# IF_SEL.net
KiCad netlist of a schematic drawn in Altium Designer
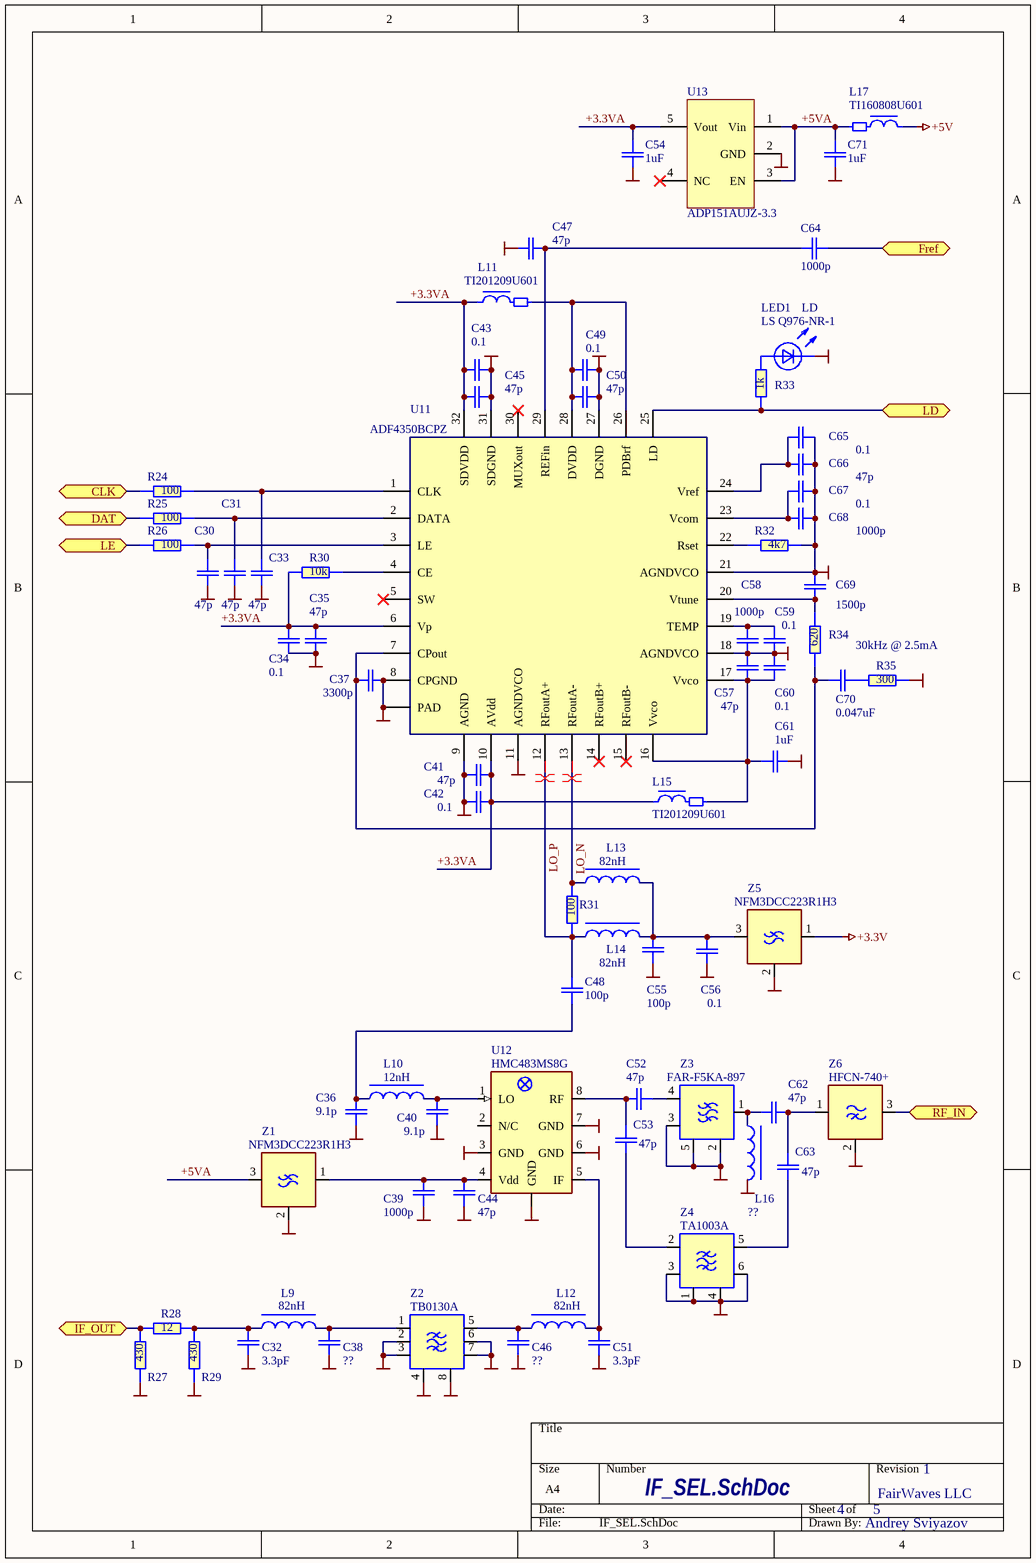
[diagram p0: IF_SEL.SchDoc]

(export (version "E")
  (design (tool "Eeschema 10.0.6"))
  (components
    (comp (ref "C30")
      (value "47p")
      (footprint "C0603-Phillips")
      (description "Capacitor")
      (fields (field (name "MANUFACTURER") "MURATA") (field (name "TOLERANCE") "20%"))
      (libsource (lib "Capacitors") (part "C0603"))
    )
    (comp (ref "C31")
      (value "47p")
      (footprint "C0603-Phillips")
      (description "Capacitor")
      (fields (field (name "MANUFACTURER") "MURATA") (field (name "TOLERANCE") "20%"))
      (libsource (lib "Capacitors") (part "C0603"))
    )
    (comp (ref "C32")
      (value "3.3pF")
      (footprint "C0603-Phillips")
      (description "Capacitor")
      (fields (field (name "MANUFACTURER") "MURATA") (field (name "TOLERANCE") "20%"))
      (libsource (lib "Capacitors") (part "C0603"))
    )
    (comp (ref "C33")
      (value "47p")
      (footprint "C0603-Phillips")
      (description "Capacitor")
      (fields (field (name "MANUFACTURER") "MURATA") (field (name "TOLERANCE") "20%"))
      (libsource (lib "Capacitors") (part "C0603"))
    )
    (comp (ref "C34")
      (value "0.1")
      (footprint "C0603-Phillips")
      (description "Capacitor")
      (fields (field (name "MANUFACTURER") "MURATA") (field (name "TOLERANCE") "20%"))
      (libsource (lib "Capacitors") (part "C0603"))
    )
    (comp (ref "C35")
      (value "47p")
      (footprint "C0603-Phillips")
      (description "Capacitor")
      (fields (field (name "MANUFACTURER") "MURATA") (field (name "TOLERANCE") "20%"))
      (libsource (lib "Capacitors") (part "C0603"))
    )
    (comp (ref "C36")
      (value "9.1p")
      (footprint "C0603-Phillips")
      (description "Capacitor")
      (fields (field (name "MANUFACTURER") "MURATA") (field (name "TOLERANCE") "20%"))
      (libsource (lib "Capacitors") (part "C0603"))
    )
    (comp (ref "C37")
      (value "3300p")
      (footprint "C0603-Phillips")
      (description "Capacitor")
      (fields (field (name "MANUFACTURER") "MURATA") (field (name "TOLERANCE") "20%"))
      (libsource (lib "Capacitors") (part "C0603"))
    )
    (comp (ref "C38")
      (value "??")
      (footprint "C0603-Phillips")
      (description "Capacitor")
      (fields (field (name "MANUFACTURER") "MURATA") (field (name "TOLERANCE") "20%"))
      (libsource (lib "Capacitors") (part "C0603"))
    )
    (comp (ref "C39")
      (value "1000p")
      (footprint "C0603-Phillips")
      (description "Capacitor")
      (fields (field (name "MANUFACTURER") "MURATA") (field (name "TOLERANCE") "20%"))
      (libsource (lib "Capacitors") (part "C0603"))
    )
    (comp (ref "C40")
      (value "9.1p")
      (footprint "C0603-Phillips")
      (description "Capacitor")
      (fields (field (name "MANUFACTURER") "MURATA") (field (name "TOLERANCE") "20%"))
      (libsource (lib "Capacitors") (part "C0603"))
    )
    (comp (ref "C41")
      (value "47p")
      (footprint "C0603-Phillips")
      (description "Capacitor")
      (fields (field (name "MANUFACTURER") "MURATA") (field (name "TOLERANCE") "20%"))
      (libsource (lib "Capacitors") (part "C0603"))
    )
    (comp (ref "C42")
      (value "0.1")
      (footprint "C0603-Phillips")
      (description "Capacitor")
      (fields (field (name "MANUFACTURER") "MURATA") (field (name "TOLERANCE") "20%"))
      (libsource (lib "Capacitors") (part "C0603"))
    )
    (comp (ref "C43")
      (value "0.1")
      (footprint "C0603-Phillips")
      (description "Capacitor")
      (fields (field (name "MANUFACTURER") "MURATA") (field (name "TOLERANCE") "20%"))
      (libsource (lib "Capacitors") (part "C0603"))
    )
    (comp (ref "C44")
      (value "47p")
      (footprint "C0603-Phillips")
      (description "Capacitor")
      (fields (field (name "MANUFACTURER") "MURATA") (field (name "TOLERANCE") "20%"))
      (libsource (lib "Capacitors") (part "C0603"))
    )
    (comp (ref "C45")
      (value "47p")
      (footprint "C0603-Phillips")
      (description "Capacitor")
      (fields (field (name "MANUFACTURER") "MURATA") (field (name "TOLERANCE") "20%"))
      (libsource (lib "Capacitors") (part "C0603"))
    )
    (comp (ref "C46")
      (value "??")
      (footprint "C0603-Phillips")
      (description "Capacitor")
      (fields (field (name "MANUFACTURER") "MURATA") (field (name "TOLERANCE") "20%"))
      (libsource (lib "Capacitors") (part "C0603"))
    )
    (comp (ref "C47")
      (value "47p")
      (footprint "C0603-Phillips")
      (description "Capacitor")
      (fields (field (name "MANUFACTURER") "MURATA") (field (name "TOLERANCE") "20%"))
      (libsource (lib "Capacitors") (part "C0603"))
    )
    (comp (ref "C48")
      (value "100p")
      (footprint "C0603-Phillips")
      (description "Capacitor")
      (fields (field (name "MANUFACTURER") "MURATA") (field (name "TOLERANCE") "20%"))
      (libsource (lib "Capacitors") (part "C0603"))
    )
    (comp (ref "C49")
      (value "0.1")
      (footprint "C0603-Phillips")
      (description "Capacitor")
      (fields (field (name "MANUFACTURER") "MURATA") (field (name "TOLERANCE") "20%"))
      (libsource (lib "Capacitors") (part "C0603"))
    )
    (comp (ref "C50")
      (value "47p")
      (footprint "C0603-Phillips")
      (description "Capacitor")
      (fields (field (name "MANUFACTURER") "MURATA") (field (name "TOLERANCE") "20%"))
      (libsource (lib "Capacitors") (part "C0603"))
    )
    (comp (ref "C51")
      (value "3.3pF")
      (footprint "C0603-Phillips")
      (description "Capacitor")
      (fields (field (name "MANUFACTURER") "MURATA") (field (name "TOLERANCE") "20%"))
      (libsource (lib "Capacitors") (part "C0603"))
    )
    (comp (ref "C52")
      (value "47p")
      (footprint "C0603-Phillips")
      (description "Capacitor")
      (fields (field (name "MANUFACTURER") "MURATA") (field (name "TOLERANCE") "20%"))
      (libsource (lib "Capacitors") (part "C0603"))
    )
    (comp (ref "C53")
      (value "47p")
      (footprint "C0603-Phillips")
      (description "Capacitor")
      (fields (field (name "MANUFACTURER") "MURATA") (field (name "TOLERANCE") "20%"))
      (libsource (lib "Capacitors") (part "C0603"))
    )
    (comp (ref "C54")
      (value "1uF")
      (footprint "C0603-Phillips")
      (description "Capacitor")
      (fields (field (name "MANUFACTURER") "MURATA") (field (name "TOLERANCE") "20%"))
      (libsource (lib "Capacitors") (part "C0603"))
    )
    (comp (ref "C55")
      (value "100p")
      (footprint "C0603-Phillips")
      (description "Capacitor")
      (fields (field (name "MANUFACTURER") "MURATA") (field (name "TOLERANCE") "20%"))
      (libsource (lib "Capacitors") (part "C0603"))
    )
    (comp (ref "C56")
      (value "0.1")
      (footprint "C0603-Phillips")
      (description "Capacitor")
      (fields (field (name "MANUFACTURER") "MURATA") (field (name "TOLERANCE") "20%"))
      (libsource (lib "Capacitors") (part "C0603"))
    )
    (comp (ref "C57")
      (value "47p")
      (footprint "C0603-Phillips")
      (description "Capacitor")
      (fields (field (name "MANUFACTURER") "MURATA") (field (name "TOLERANCE") "20%"))
      (libsource (lib "Capacitors") (part "C0603"))
    )
    (comp (ref "C58")
      (value "1000p")
      (footprint "C0603-Phillips")
      (description "Capacitor")
      (fields (field (name "MANUFACTURER") "MURATA") (field (name "TOLERANCE") "20%"))
      (libsource (lib "Capacitors") (part "C0603"))
    )
    (comp (ref "C59")
      (value "0.1")
      (footprint "C0603-Phillips")
      (description "Capacitor")
      (fields (field (name "MANUFACTURER") "MURATA") (field (name "TOLERANCE") "20%"))
      (libsource (lib "Capacitors") (part "C0603"))
    )
    (comp (ref "C60")
      (value "0.1")
      (footprint "C0603-Phillips")
      (description "Capacitor")
      (fields (field (name "MANUFACTURER") "MURATA") (field (name "TOLERANCE") "20%"))
      (libsource (lib "Capacitors") (part "C0603"))
    )
    (comp (ref "C61")
      (value "1uF")
      (footprint "C0603-Phillips")
      (description "Capacitor")
      (fields (field (name "MANUFACTURER") "MURATA") (field (name "TOLERANCE") "20%"))
      (libsource (lib "Capacitors") (part "C0603"))
    )
    (comp (ref "C62")
      (value "47p")
      (footprint "C0603-Phillips")
      (description "Capacitor")
      (fields (field (name "MANUFACTURER") "MURATA") (field (name "TOLERANCE") "20%"))
      (libsource (lib "Capacitors") (part "C0603"))
    )
    (comp (ref "C63")
      (value "47p")
      (footprint "C0603-Phillips")
      (description "Capacitor")
      (fields (field (name "MANUFACTURER") "MURATA") (field (name "TOLERANCE") "20%"))
      (libsource (lib "Capacitors") (part "C0603"))
    )
    (comp (ref "C64")
      (value "1000p")
      (footprint "C0603-Phillips")
      (description "Capacitor")
      (fields (field (name "MANUFACTURER") "MURATA") (field (name "TOLERANCE") "20%"))
      (libsource (lib "Capacitors") (part "C0603"))
    )
    (comp (ref "C65")
      (value "0.1")
      (footprint "C0603-Phillips")
      (description "Capacitor")
      (fields (field (name "MANUFACTURER") "MURATA") (field (name "TOLERANCE") "20%"))
      (libsource (lib "Capacitors") (part "C0603"))
    )
    (comp (ref "C66")
      (value "47p")
      (footprint "C0603-Phillips")
      (description "Capacitor")
      (fields (field (name "MANUFACTURER") "MURATA") (field (name "TOLERANCE") "20%"))
      (libsource (lib "Capacitors") (part "C0603"))
    )
    (comp (ref "C67")
      (value "0.1")
      (footprint "C0603-Phillips")
      (description "Capacitor")
      (fields (field (name "MANUFACTURER") "MURATA") (field (name "TOLERANCE") "20%"))
      (libsource (lib "Capacitors") (part "C0603"))
    )
    (comp (ref "C68")
      (value "1000p")
      (footprint "C0603-Phillips")
      (description "Capacitor")
      (fields (field (name "MANUFACTURER") "MURATA") (field (name "TOLERANCE") "20%"))
      (libsource (lib "Capacitors") (part "C0603"))
    )
    (comp (ref "C69")
      (value "1500p")
      (footprint "C0603-Phillips")
      (description "Capacitor")
      (fields (field (name "MANUFACTURER") "MURATA") (field (name "TOLERANCE") "20%"))
      (libsource (lib "Capacitors") (part "C0603"))
    )
    (comp (ref "C70")
      (value "0.047uF")
      (footprint "C0603-Phillips")
      (description "Capacitor")
      (fields (field (name "MANUFACTURER") "MURATA") (field (name "TOLERANCE") "20%"))
      (libsource (lib "Capacitors") (part "C0603"))
    )
    (comp (ref "C71")
      (value "1uF")
      (footprint "C0603-Phillips")
      (description "Capacitor")
      (fields (field (name "MANUFACTURER") "MURATA") (field (name "TOLERANCE") "20%"))
      (libsource (lib "Capacitors") (part "C0603"))
    )
    (comp (ref "L9")
      (value "82nH")
      (footprint "TF160808-Phillips")
      (description "Coil")
      (fields (field (name "MANUFACTURER") "SMD"))
      (libsource (lib "Inductance Transformers") (part "TF160808"))
    )
    (comp (ref "L10")
      (value "12nH")
      (footprint "TF160808-Phillips")
      (description "Coil")
      (fields (field (name "MANUFACTURER") "SMD"))
      (libsource (lib "") (part "TF160808_1"))
    )
    (comp (ref "L11")
      (value "TI201209U601")
      (footprint "TI2012-Phillips")
      (description "Choke")
      (fields (field (name "MANUFACTURER") "MURATA"))
      (libsource (lib "Andy") (part "TI2012_1"))
    )
    (comp (ref "L12")
      (value "82nH")
      (footprint "TF160808-Phillips")
      (description "Coil")
      (fields (field (name "MANUFACTURER") "SMD"))
      (libsource (lib "Inductance Transformers") (part "TF160808"))
    )
    (comp (ref "L13")
      (value "82nH")
      (footprint "TF160808-Phillips")
      (description "Coil")
      (fields (field (name "MANUFACTURER") "SMD"))
      (libsource (lib "Inductance Transformers") (part "TF160808"))
    )
    (comp (ref "L14")
      (value "82nH")
      (footprint "TF160808-Phillips")
      (description "Coil")
      (fields (field (name "MANUFACTURER") "SMD"))
      (libsource (lib "Inductance Transformers") (part "TF160808"))
    )
    (comp (ref "L15")
      (value "TI201209U601")
      (footprint "TI2012-Phillips")
      (description "Choke")
      (fields (field (name "MANUFACTURER") "MURATA"))
      (libsource (lib "Andy") (part "TI2012_1"))
    )
    (comp (ref "L16")
      (value "??")
      (footprint "TF160808-Phillips")
      (description "Coil")
      (fields (field (name "MANUFACTURER") "SMD"))
      (libsource (lib "Inductance Transformers") (part "TF160808"))
    )
    (comp (ref "L17")
      (value "TI160808U601")
      (footprint "Andy:Ti160808-Phillips")
      (description "Choke")
      (fields (field (name "MANUFACTURER") "MURATA"))
      (libsource (lib "altium-import") (part "root_0_mirrored_TI160808_"))
    )
    (comp (ref "LED1")
      (value "LS Q976-NR-1")
      (footprint "LED-0603y")
      (description "LED SMD")
      (fields (field (name "MANUFACTURER") "OSRAM Opto Semi") (field (name "MISC") "LD"))
      (libsource (lib "altium-import") (part "root_1_mirrored_LED0603_"))
    )
    (comp (ref "R24")
      (value "100")
      (footprint "R0603-PHILLIPS")
      (description "Resistor")
      (fields (field (name "MANUFACTURER") "YAGEO") (field (name "TOLERANCE") "5%"))
      (libsource (lib "altium-import") (part "root_1_R0603_"))
    )
    (comp (ref "R25")
      (value "100")
      (footprint "R0603-PHILLIPS")
      (description "Resistor")
      (fields (field (name "MANUFACTURER") "YAGEO") (field (name "TOLERANCE") "5%"))
      (libsource (lib "altium-import") (part "root_1_R0603_"))
    )
    (comp (ref "R26")
      (value "100")
      (footprint "R0603-PHILLIPS")
      (description "Resistor")
      (fields (field (name "MANUFACTURER") "YAGEO") (field (name "TOLERANCE") "5%"))
      (libsource (lib "altium-import") (part "root_1_R0603_"))
    )
    (comp (ref "R27")
      (value "430")
      (footprint "R0603-PHILLIPS")
      (description "Resistor")
      (fields (field (name "MANUFACTURER") "YAGEO") (field (name "TOLERANCE") "5%"))
      (libsource (lib "altium-import") (part "root_2_R0603_"))
    )
    (comp (ref "R28")
      (value "12")
      (footprint "R0603-PHILLIPS")
      (description "Resistor")
      (fields (field (name "MANUFACTURER") "YAGEO") (field (name "TOLERANCE") "5%"))
      (libsource (lib "altium-import") (part "root_1_R0603_"))
    )
    (comp (ref "R29")
      (value "430")
      (footprint "R0603-PHILLIPS")
      (description "Resistor")
      (fields (field (name "MANUFACTURER") "YAGEO") (field (name "TOLERANCE") "5%"))
      (libsource (lib "altium-import") (part "root_2_R0603_"))
    )
    (comp (ref "R30")
      (value "10k")
      (footprint "R0603-PHILLIPS")
      (description "Resistor")
      (fields (field (name "MANUFACTURER") "YAGEO") (field (name "TOLERANCE") "5%"))
      (libsource (lib "altium-import") (part "root_1_R0603_"))
    )
    (comp (ref "R31")
      (value "100")
      (footprint "R0603-PHILLIPS")
      (description "Resistor")
      (fields (field (name "MANUFACTURER") "YAGEO") (field (name "TOLERANCE") "5%"))
      (libsource (lib "altium-import") (part "root_2_R0603_"))
    )
    (comp (ref "R32")
      (value "4k7")
      (footprint "R0603-PHILLIPS")
      (description "Resistor")
      (fields (field (name "MANUFACTURER") "YAGEO") (field (name "TOLERANCE") "5%"))
      (libsource (lib "altium-import") (part "root_1_R0603_"))
    )
    (comp (ref "R33")
      (value "1k")
      (footprint "R0603-PHILLIPS")
      (description "Resistor")
      (fields (field (name "MANUFACTURER") "YAGEO") (field (name "TOLERANCE") "5%"))
      (libsource (lib "altium-import") (part "root_2_R0603_"))
    )
    (comp (ref "R34")
      (value "620")
      (footprint "R0603-PHILLIPS")
      (description "Resistor")
      (fields (field (name "MANUFACTURER") "YAGEO") (field (name "TOLERANCE") "5%"))
      (libsource (lib "altium-import") (part "root_2_R0603_"))
    )
    (comp (ref "R35")
      (value "300")
      (footprint "R0603-PHILLIPS")
      (description "Resistor")
      (fields (field (name "MANUFACTURER") "YAGEO") (field (name "TOLERANCE") "5%"))
      (libsource (lib "altium-import") (part "root_1_R0603_"))
    )
    (comp (ref "U11")
      (value "ADF4350BCPZ")
      (footprint "CP-32-2")
      (description "IC")
      (fields (field (name "MANUFACTURER") "Analog Devices"))
      (libsource (lib "Andy") (part "ADF4350BCPZ"))
    )
    (comp (ref "U12")
      (value "HMC483MS8G")
      (footprint "MS8G")
      (description "IC")
      (fields (field (name "MANUFACTURER") "Hittite"))
      (libsource (lib "MicroCircuits") (part "HMC483_5MS8G"))
    )
    (comp (ref "U13")
      (value "ADP151AUJZ-3.3")
      (footprint "SOT-23-5[3.1x1.8/0.95]")
      (description "IC")
      (fields (field (name "MANUFACTURER") "AD"))
      (libsource (lib "Andy") (part "ADP151AUJZ"))
    )
    (comp (ref "Z1")
      (value "NFM3DCC223R1H3")
      (footprint "NFM3DC")
      (description "EMI_FILTER")
      (fields (field (name "MANUFACTURER") "Murata"))
      (libsource (lib "Andy") (part "NFM3DC"))
    )
    (comp (ref "Z2")
      (value "TB0130A")
      (footprint "DCC8_5x5")
      (description "SAW filter")
      (fields (field (name "MANUFACTURER") "Tai-SAW"))
      (libsource (lib "Andy") (part "SAW 5x5-8 SMD"))
    )
    (comp (ref "Z3")
      (value "FAR-F5KA-897")
      (footprint "SAW-1.4x1x0.5mm")
      (description "SAW Filter")
      (fields (field (name "MANUFACTURER") "Taiyo Yuden"))
      (libsource (lib "Andy") (part "SAW 1.4x1.0-5 SMD"))
    )
    (comp (ref "Z4")
      (value "TA1003A")
      (footprint "DCC6C_L")
      (description "SAW filter")
      (fields (field (name "MANUFACTURER") "Tai-SAW"))
      (libsource (lib "Andy") (part "SAW 3x3 SMD"))
    )
    (comp (ref "Z5")
      (value "NFM3DCC223R1H3")
      (footprint "NFM3DC")
      (description "EMI_FILTER")
      (fields (field (name "MANUFACTURER") "Murata"))
      (libsource (lib "Andy") (part "NFM3DC"))
    )
    (comp (ref "Z6")
      (value "HFCN-740+")
      (footprint "LFCN-HFCN")
      (description "High pass filter")
      (fields (field (name "MANUFACTURER") "MiniCircuits"))
      (libsource (lib "Andy") (part "HFCN-2700"))
    )
  )
  (nets
    (net (code "1") (name "+3.3V") (class "Default")
      (node (ref "Z5") (pin "1") (pinfunction "1_1") (pintype "passive"))
    )
    (net (code "2") (name "+5V") (class "Default")
      (node (ref "L17") (pin "1") (pinfunction "1_1") (pintype "passive"))
    )
    (net (code "3") (name "/+3.3VA") (class "Default")
      (node (ref "C34") (pin "2") (pinfunction "2_2") (pintype "passive"))
      (node (ref "C35") (pin "2") (pinfunction "2_2") (pintype "passive"))
      (node (ref "C41") (pin "1") (pinfunction "1_1") (pintype "passive"))
      (node (ref "C42") (pin "1") (pinfunction "1_1") (pintype "passive"))
      (node (ref "C43") (pin "1") (pinfunction "1_1") (pintype "passive"))
      (node (ref "C45") (pin "1") (pinfunction "1_1") (pintype "passive"))
      (node (ref "C54") (pin "2") (pinfunction "2_2") (pintype "passive"))
      (node (ref "L11") (pin "1") (pinfunction "1_1") (pintype "passive"))
      (node (ref "L15") (pin "1") (pinfunction "1_1") (pintype "passive"))
      (node (ref "R30") (pin "1") (pinfunction "1_1") (pintype "passive"))
      (node (ref "U11") (pin "10") (pinfunction "AVdd_10") (pintype "power_in"))
      (node (ref "U11") (pin "32") (pinfunction "SDVDD_32") (pintype "power_in"))
      (node (ref "U11") (pin "6") (pinfunction "Vp_6") (pintype "passive"))
      (node (ref "U13") (pin "5") (pinfunction "Vout_5") (pintype "passive"))
    )
    (net (code "4") (name "/+5VA") (class "Default")
      (node (ref "C71") (pin "2") (pinfunction "2_2") (pintype "passive"))
      (node (ref "L17") (pin "2") (pinfunction "2_2") (pintype "passive"))
      (node (ref "U13") (pin "1") (pinfunction "Vin_1") (pintype "passive"))
      (node (ref "U13") (pin "3") (pinfunction "EN_3") (pintype "passive"))
      (node (ref "Z1") (pin "3") (pinfunction "3_3") (pintype "passive"))
    )
    (net (code "5") (name "/CLK") (class "Default")
      (node (ref "R24") (pin "1") (pinfunction "1_1") (pintype "passive"))
    )
    (net (code "6") (name "/DAT") (class "Default")
      (node (ref "R25") (pin "1") (pinfunction "1_1") (pintype "passive"))
    )
    (net (code "7") (name "/Fref") (class "Default")
      (node (ref "C64") (pin "2") (pinfunction "2_2") (pintype "passive"))
    )
    (net (code "8") (name "/IF_OUT") (class "Default")
      (node (ref "R27") (pin "2") (pinfunction "2_2") (pintype "passive"))
      (node (ref "R28") (pin "1") (pinfunction "1_1") (pintype "passive"))
    )
    (net (code "9") (name "/LD") (class "Default")
      (node (ref "R33") (pin "1") (pinfunction "1_1") (pintype "passive"))
      (node (ref "U11") (pin "25") (pinfunction "LD_25") (pintype "passive"))
    )
    (net (code "10") (name "/LE") (class "Default")
      (node (ref "R26") (pin "1") (pinfunction "1_1") (pintype "passive"))
    )
    (net (code "11") (name "/LO_N") (class "Default")
      (node (ref "L13") (pin "1") (pinfunction "1_1") (pintype "passive"))
      (node (ref "R31") (pin "2") (pinfunction "2_2") (pintype "passive"))
      (node (ref "U11") (pin "13") (pinfunction "RFoutA-_13") (pintype "passive"))
    )
    (net (code "12") (name "/LO_P") (class "Default")
      (node (ref "C48") (pin "1") (pinfunction "1_1") (pintype "passive"))
      (node (ref "L14") (pin "1") (pinfunction "1_1") (pintype "passive"))
      (node (ref "R31") (pin "1") (pinfunction "1_1") (pintype "passive"))
      (node (ref "U11") (pin "12") (pinfunction "RFoutA+_12") (pintype "passive"))
    )
    (net (code "13") (name "/RF_IN") (class "Default")
      (node (ref "Z6") (pin "3") (pinfunction "3_3") (pintype "passive"))
    )
    (net (code "14") (name "GND") (class "Default")
      (node (ref "C30") (pin "1") (pinfunction "1_1") (pintype "passive"))
      (node (ref "C31") (pin "1") (pinfunction "1_1") (pintype "passive"))
      (node (ref "C32") (pin "1") (pinfunction "1_1") (pintype "passive"))
      (node (ref "C33") (pin "1") (pinfunction "1_1") (pintype "passive"))
      (node (ref "C34") (pin "1") (pinfunction "1_1") (pintype "passive"))
      (node (ref "C35") (pin "1") (pinfunction "1_1") (pintype "passive"))
      (node (ref "C36") (pin "2") (pinfunction "2_2") (pintype "passive"))
      (node (ref "C37") (pin "1") (pinfunction "1_1") (pintype "passive"))
      (node (ref "C38") (pin "1") (pinfunction "1_1") (pintype "passive"))
      (node (ref "C39") (pin "2") (pinfunction "2_2") (pintype "passive"))
      (node (ref "C40") (pin "2") (pinfunction "2_2") (pintype "passive"))
      (node (ref "C41") (pin "2") (pinfunction "2_2") (pintype "passive"))
      (node (ref "C42") (pin "2") (pinfunction "2_2") (pintype "passive"))
      (node (ref "C43") (pin "2") (pinfunction "2_2") (pintype "passive"))
      (node (ref "C44") (pin "2") (pinfunction "2_2") (pintype "passive"))
      (node (ref "C45") (pin "2") (pinfunction "2_2") (pintype "passive"))
      (node (ref "C46") (pin "1") (pinfunction "1_1") (pintype "passive"))
      (node (ref "C47") (pin "1") (pinfunction "1_1") (pintype "passive"))
      (node (ref "C49") (pin "2") (pinfunction "2_2") (pintype "passive"))
      (node (ref "C50") (pin "2") (pinfunction "2_2") (pintype "passive"))
      (node (ref "C51") (pin "1") (pinfunction "1_1") (pintype "passive"))
      (node (ref "C54") (pin "1") (pinfunction "1_1") (pintype "passive"))
      (node (ref "C55") (pin "2") (pinfunction "2_2") (pintype "passive"))
      (node (ref "C56") (pin "1") (pinfunction "1_1") (pintype "passive"))
      (node (ref "C57") (pin "2") (pinfunction "2_2") (pintype "passive"))
      (node (ref "C58") (pin "1") (pinfunction "1_1") (pintype "passive"))
      (node (ref "C59") (pin "1") (pinfunction "1_1") (pintype "passive"))
      (node (ref "C60") (pin "2") (pinfunction "2_2") (pintype "passive"))
      (node (ref "C61") (pin "1") (pinfunction "1_1") (pintype "passive"))
      (node (ref "C65") (pin "2") (pinfunction "2_2") (pintype "passive"))
      (node (ref "C66") (pin "2") (pinfunction "2_2") (pintype "passive"))
      (node (ref "C67") (pin "2") (pinfunction "2_2") (pintype "passive"))
      (node (ref "C68") (pin "2") (pinfunction "2_2") (pintype "passive"))
      (node (ref "C69") (pin "2") (pinfunction "2_2") (pintype "passive"))
      (node (ref "C71") (pin "1") (pinfunction "1_1") (pintype "passive"))
      (node (ref "L16") (pin "2") (pinfunction "2_2") (pintype "passive"))
      (node (ref "LED1") (pin "1") (pinfunction "K_1") (pintype "passive"))
      (node (ref "R27") (pin "1") (pinfunction "1_1") (pintype "passive"))
      (node (ref "R29") (pin "1") (pinfunction "1_1") (pintype "passive"))
      (node (ref "R32") (pin "2") (pinfunction "2_2") (pintype "passive"))
      (node (ref "R35") (pin "2") (pinfunction "2_2") (pintype "passive"))
      (node (ref "U11") (pin "0") (pinfunction "PAD_0") (pintype "passive"))
      (node (ref "U11") (pin "11") (pinfunction "AGNDVCO_11") (pintype "power_in"))
      (node (ref "U11") (pin "18") (pinfunction "AGNDVCO_18") (pintype "power_in"))
      (node (ref "U11") (pin "21") (pinfunction "AGNDVCO_21") (pintype "power_in"))
      (node (ref "U11") (pin "27") (pinfunction "DGND_27") (pintype "power_in"))
      (node (ref "U11") (pin "31") (pinfunction "SDGND_31") (pintype "power_in"))
      (node (ref "U11") (pin "8") (pinfunction "CPGND_8") (pintype "passive"))
      (node (ref "U11") (pin "9") (pinfunction "AGND_9") (pintype "power_in"))
      (node (ref "U12") (pin "0") (pinfunction "GND_0") (pintype "power_in"))
      (node (ref "U12") (pin "3") (pinfunction "GND_3") (pintype "power_in"))
      (node (ref "U12") (pin "6") (pinfunction "GND_6") (pintype "power_in"))
      (node (ref "U12") (pin "7") (pinfunction "GND_7") (pintype "power_in"))
      (node (ref "U13") (pin "2") (pinfunction "GND_2") (pintype "passive"))
      (node (ref "Z1") (pin "2") (pinfunction "2_2") (pintype "passive"))
      (node (ref "Z2") (pin "2") (pinfunction "In2_2") (pintype "power_in"))
      (node (ref "Z2") (pin "3") (pinfunction "In3_3") (pintype "power_in"))
      (node (ref "Z2") (pin "4") (pinfunction "Gnd_4") (pintype "power_in"))
      (node (ref "Z2") (pin "6") (pinfunction "Out2_6") (pintype "power_in"))
      (node (ref "Z2") (pin "7") (pinfunction "Out3_7") (pintype "power_in"))
      (node (ref "Z2") (pin "8") (pinfunction "Gnd_8") (pintype "power_in"))
      (node (ref "Z3") (pin "2") (pinfunction "GND_2") (pintype "power_in"))
      (node (ref "Z3") (pin "3") (pinfunction "~{Out}_3") (pintype "passive"))
      (node (ref "Z3") (pin "5") (pinfunction "GND_5") (pintype "power_in"))
      (node (ref "Z4") (pin "1") (pinfunction "GND_1") (pintype "power_in"))
      (node (ref "Z4") (pin "3") (pinfunction "GND_3") (pintype "power_in"))
      (node (ref "Z4") (pin "4") (pinfunction "GND_4") (pintype "power_in"))
      (node (ref "Z4") (pin "6") (pinfunction "GND_6") (pintype "power_in"))
      (node (ref "Z5") (pin "2") (pinfunction "2_2") (pintype "passive"))
      (node (ref "Z6") (pin "2") (pinfunction "2_2") (pintype "passive"))
    )
    (net (code "15") (name "Net-(C32-Pad2)") (class "Default")
      (node (ref "C32") (pin "2") (pinfunction "2_2") (pintype "passive"))
      (node (ref "L9") (pin "1") (pinfunction "1_1") (pintype "passive"))
      (node (ref "R28") (pin "2") (pinfunction "2_2") (pintype "passive"))
      (node (ref "R29") (pin "2") (pinfunction "2_2") (pintype "passive"))
    )
    (net (code "16") (name "Net-(C36-Pad1)") (class "Default")
      (node (ref "C36") (pin "1") (pinfunction "1_1") (pintype "passive"))
      (node (ref "C48") (pin "2") (pinfunction "2_2") (pintype "passive"))
      (node (ref "L10") (pin "2") (pinfunction "2_2") (pintype "passive"))
    )
    (net (code "17") (name "Net-(C55-Pad1)") (class "Default")
      (node (ref "C55") (pin "1") (pinfunction "1_1") (pintype "passive"))
      (node (ref "C56") (pin "2") (pinfunction "2_2") (pintype "passive"))
      (node (ref "L13") (pin "2") (pinfunction "2_2") (pintype "passive"))
      (node (ref "L14") (pin "2") (pinfunction "2_2") (pintype "passive"))
      (node (ref "Z5") (pin "3") (pinfunction "3_3") (pintype "passive"))
    )
    (net (code "18") (name "Net-(C57-Pad1)") (class "Default")
      (node (ref "C57") (pin "1") (pinfunction "1_1") (pintype "passive"))
      (node (ref "C60") (pin "1") (pinfunction "1_1") (pintype "passive"))
      (node (ref "C61") (pin "2") (pinfunction "2_2") (pintype "passive"))
      (node (ref "L15") (pin "2") (pinfunction "2_2") (pintype "passive"))
      (node (ref "U11") (pin "16") (pinfunction "Vvco_16") (pintype "passive"))
      (node (ref "U11") (pin "17") (pinfunction "Vvco_17") (pintype "passive"))
    )
    (net (code "19") (name "Net-(C62-Pad2)") (class "Default")
      (node (ref "C62") (pin "2") (pinfunction "2_2") (pintype "passive"))
      (node (ref "C63") (pin "2") (pinfunction "2_2") (pintype "passive"))
      (node (ref "Z6") (pin "1") (pinfunction "1_1") (pintype "passive"))
    )
    (net (code "20") (name "Net-(C70-Pad1)") (class "Default")
      (node (ref "C70") (pin "1") (pinfunction "1_1") (pintype "passive"))
      (node (ref "R35") (pin "1") (pinfunction "1_1") (pintype "passive"))
    )
    (net (code "21") (name "Net-(LED1-A)") (class "Default")
      (node (ref "LED1") (pin "2") (pinfunction "A_2") (pintype "passive"))
      (node (ref "R33") (pin "2") (pinfunction "2_2") (pintype "passive"))
    )
    (net (code "22") (name "Net-(U11-CE)") (class "Default")
      (node (ref "R30") (pin "2") (pinfunction "2_2") (pintype "passive"))
      (node (ref "U11") (pin "4") (pinfunction "CE_4") (pintype "passive"))
    )
    (net (code "23") (name "Net-(U11-CLK)") (class "Default")
      (node (ref "C33") (pin "2") (pinfunction "2_2") (pintype "passive"))
      (node (ref "R24") (pin "2") (pinfunction "2_2") (pintype "passive"))
      (node (ref "U11") (pin "1") (pinfunction "CLK_1") (pintype "passive"))
    )
    (net (code "24") (name "Net-(U11-CPout)") (class "Default")
      (node (ref "C37") (pin "2") (pinfunction "2_2") (pintype "passive"))
      (node (ref "C70") (pin "2") (pinfunction "2_2") (pintype "passive"))
      (node (ref "R34") (pin "1") (pinfunction "1_1") (pintype "passive"))
      (node (ref "U11") (pin "7") (pinfunction "CPout_7") (pintype "passive"))
    )
    (net (code "25") (name "Net-(U11-DATA)") (class "Default")
      (node (ref "C31") (pin "2") (pinfunction "2_2") (pintype "passive"))
      (node (ref "R25") (pin "2") (pinfunction "2_2") (pintype "passive"))
      (node (ref "U11") (pin "2") (pinfunction "DATA_2") (pintype "passive"))
    )
    (net (code "26") (name "Net-(U11-DVDD)") (class "Default")
      (node (ref "C49") (pin "1") (pinfunction "1_1") (pintype "passive"))
      (node (ref "C50") (pin "1") (pinfunction "1_1") (pintype "passive"))
      (node (ref "L11") (pin "2") (pinfunction "2_2") (pintype "passive"))
      (node (ref "U11") (pin "26") (pinfunction "PDBrf_26") (pintype "passive"))
      (node (ref "U11") (pin "28") (pinfunction "DVDD_28") (pintype "power_in"))
    )
    (net (code "27") (name "Net-(U11-LE)") (class "Default")
      (node (ref "C30") (pin "2") (pinfunction "2_2") (pintype "passive"))
      (node (ref "R26") (pin "2") (pinfunction "2_2") (pintype "passive"))
      (node (ref "U11") (pin "3") (pinfunction "LE_3") (pintype "passive"))
    )
    (net (code "28") (name "Net-(U11-REFin)") (class "Default")
      (node (ref "C47") (pin "2") (pinfunction "2_2") (pintype "passive"))
      (node (ref "C64") (pin "1") (pinfunction "1_1") (pintype "passive"))
      (node (ref "U11") (pin "29") (pinfunction "REFin_29") (pintype "passive"))
    )
    (net (code "29") (name "Net-(U11-Rset)") (class "Default")
      (node (ref "R32") (pin "1") (pinfunction "1_1") (pintype "passive"))
      (node (ref "U11") (pin "22") (pinfunction "Rset_22") (pintype "passive"))
    )
    (net (code "30") (name "Net-(U11-TEMP)") (class "Default")
      (node (ref "C58") (pin "2") (pinfunction "2_2") (pintype "passive"))
      (node (ref "C59") (pin "2") (pinfunction "2_2") (pintype "passive"))
      (node (ref "U11") (pin "19") (pinfunction "TEMP_19") (pintype "passive"))
    )
    (net (code "31") (name "Net-(U11-Vcom)") (class "Default")
      (node (ref "C67") (pin "1") (pinfunction "1_1") (pintype "passive"))
      (node (ref "C68") (pin "1") (pinfunction "1_1") (pintype "passive"))
      (node (ref "U11") (pin "23") (pinfunction "Vcom_23") (pintype "passive"))
    )
    (net (code "32") (name "Net-(U11-Vref)") (class "Default")
      (node (ref "C65") (pin "1") (pinfunction "1_1") (pintype "passive"))
      (node (ref "C66") (pin "1") (pinfunction "1_1") (pintype "passive"))
      (node (ref "U11") (pin "24") (pinfunction "Vref_24") (pintype "passive"))
    )
    (net (code "33") (name "Net-(U11-Vtune)") (class "Default")
      (node (ref "C69") (pin "1") (pinfunction "1_1") (pintype "passive"))
      (node (ref "R34") (pin "2") (pinfunction "2_2") (pintype "passive"))
      (node (ref "U11") (pin "20") (pinfunction "Vtune_20") (pintype "passive"))
    )
    (net (code "34") (name "Net-(U12-IF)") (class "Default")
      (node (ref "C51") (pin "2") (pinfunction "2_2") (pintype "passive"))
      (node (ref "L12") (pin "2") (pinfunction "2_2") (pintype "passive"))
      (node (ref "U12") (pin "5") (pinfunction "IF_5") (pintype "bidirectional"))
    )
    (net (code "35") (name "Net-(U12-LO)") (class "Default")
      (node (ref "C40") (pin "1") (pinfunction "1_1") (pintype "passive"))
      (node (ref "L10") (pin "1") (pinfunction "1_1") (pintype "passive"))
      (node (ref "U12") (pin "1") (pinfunction "LO_1") (pintype "input"))
    )
    (net (code "36") (name "Net-(U12-RF)") (class "Default")
      (node (ref "C52") (pin "1") (pinfunction "1_1") (pintype "passive"))
      (node (ref "C53") (pin "2") (pinfunction "2_2") (pintype "passive"))
      (node (ref "U12") (pin "8") (pinfunction "RF_8") (pintype "bidirectional"))
    )
    (net (code "37") (name "Net-(U12-Vdd)") (class "Default")
      (node (ref "C39") (pin "1") (pinfunction "1_1") (pintype "passive"))
      (node (ref "C44") (pin "1") (pinfunction "1_1") (pintype "passive"))
      (node (ref "U12") (pin "4") (pinfunction "Vdd_4") (pintype "power_in"))
      (node (ref "Z1") (pin "1") (pinfunction "1_1") (pintype "passive"))
    )
    (net (code "38") (name "Net-(Z2-IN1)") (class "Default")
      (node (ref "C38") (pin "2") (pinfunction "2_2") (pintype "passive"))
      (node (ref "L9") (pin "2") (pinfunction "2_2") (pintype "passive"))
      (node (ref "Z2") (pin "1") (pinfunction "IN1_1") (pintype "passive"))
    )
    (net (code "39") (name "Net-(Z2-Out1)") (class "Default")
      (node (ref "C46") (pin "2") (pinfunction "2_2") (pintype "passive"))
      (node (ref "L12") (pin "1") (pinfunction "1_1") (pintype "passive"))
      (node (ref "Z2") (pin "5") (pinfunction "Out1_5") (pintype "passive"))
    )
    (net (code "40") (name "Net-(Z3-IN)") (class "Default")
      (node (ref "C62") (pin "1") (pinfunction "1_1") (pintype "passive"))
      (node (ref "L16") (pin "1") (pinfunction "1_1") (pintype "passive"))
      (node (ref "Z3") (pin "1") (pinfunction "IN_1") (pintype "passive"))
    )
    (net (code "41") (name "Net-(Z3-Out)") (class "Default")
      (node (ref "C52") (pin "2") (pinfunction "2_2") (pintype "passive"))
      (node (ref "Z3") (pin "4") (pinfunction "Out_4") (pintype "passive"))
    )
    (net (code "42") (name "Net-(Z4-IN)") (class "Default")
      (node (ref "C53") (pin "1") (pinfunction "1_1") (pintype "passive"))
      (node (ref "Z4") (pin "2") (pinfunction "IN_2") (pintype "passive"))
    )
    (net (code "43") (name "Net-(Z4-Out)") (class "Default")
      (node (ref "C63") (pin "1") (pinfunction "1_1") (pintype "passive"))
      (node (ref "Z4") (pin "5") (pinfunction "Out_5") (pintype "passive"))
    )
    (net (code "44") (name "unconnected-(U11-MUXout-Pad30)") (class "Default")
      (node (ref "U11") (pin "30") (pinfunction "MUXout_30") (pintype "passive+no_connect"))
    )
    (net (code "45") (name "unconnected-(U11-RFoutB+-Pad14)") (class "Default")
      (node (ref "U11") (pin "14") (pinfunction "RFoutB+_14") (pintype "passive+no_connect"))
    )
    (net (code "46") (name "unconnected-(U11-RFoutB--Pad15)") (class "Default")
      (node (ref "U11") (pin "15") (pinfunction "RFoutB-_15") (pintype "passive+no_connect"))
    )
    (net (code "47") (name "unconnected-(U11-SW-Pad5)") (class "Default")
      (node (ref "U11") (pin "5") (pinfunction "SW_5") (pintype "passive+no_connect"))
    )
    (net (code "48") (name "unconnected-(U12-N{slash}C-Pad2)") (class "Default")
      (node (ref "U12") (pin "2") (pinfunction "N/C_2") (pintype "passive"))
    )
    (net (code "49") (name "unconnected-(U13-NC-Pad4)") (class "Default")
      (node (ref "U13") (pin "4") (pinfunction "NC_4") (pintype "passive+no_connect"))
    )
  )
)
